# EPS_MPPT_X_OR_MPB.net
KiCad netlist of a schematic drawn in Altium Designer
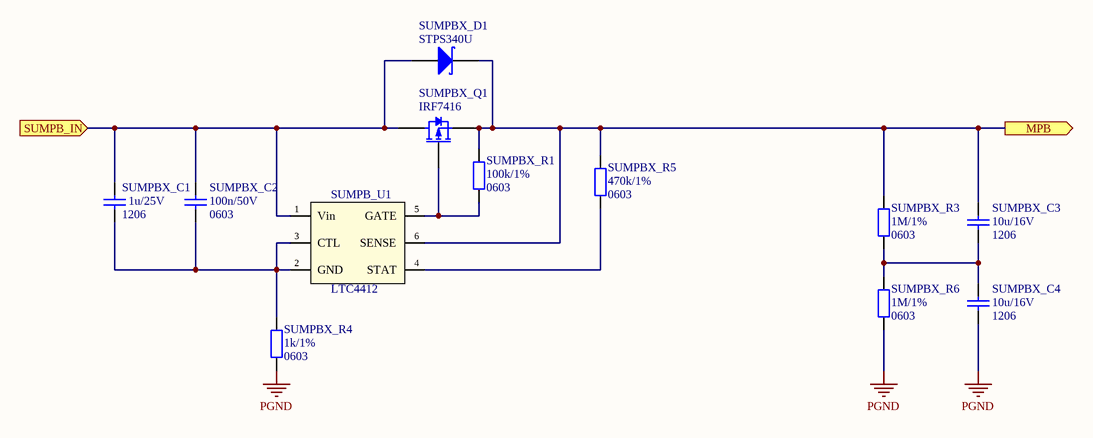
[diagram p0: EPS_MPPT_X_OR_MPB.SchDoc]

(export (version "E")
  (design (tool "Eeschema 10.0.6"))
  (components
    (comp (ref "SUMPBX_C1")
      (value "1u/25V")
      (footprint "SMD_Capacitor_1206")
      (description "Ceramic Cap Kemet COTS 1u/25V X7R 1206")
      (fields
        (field (name "MANUFACTURERPARTNUMBER") "C1206T105K3RALTU")
        (field (name "MANUFACTURER") "Kemet")
        (field (name "PACKAGE") "1206")
      )
      (libsource (lib "capacitors") (part "Cer_C1206T105K3RALTU"))
    )
    (comp (ref "SUMPBX_C2")
      (value "100n/50V")
      (footprint "SMD_Capacitor_0603")
      (description "Ceramic Cap Murata Automotive 100n/50V X7R 0603")
      (fields
        (field (name "MANUFACTURER") "Murata")
        (field (name "MANUFACTURERPARTNUMBER") "GCJ188R71H104KA12D")
        (field (name "PACKAGE") "0603")
      )
      (libsource (lib "capacitors") (part "Cer_GCJ188R71H104KA12D"))
    )
    (comp (ref "SUMPBX_C3")
      (value "10u/16V")
      (footprint "SMD_Capacitor_1206")
      (description "Ceramic Cap Kemet COTS 10u/16V X7R 1206")
      (fields
        (field (name "MANUFACTURERPARTNUMBER") "C1206T106K4RACTU")
        (field (name "MANUFACTURER") "Kemet")
        (field (name "PACKGE") "1206")
      )
      (libsource (lib "capacitors") (part "Cer_C1206T106K4RACTU"))
    )
    (comp (ref "SUMPBX_C4")
      (value "10u/16V")
      (footprint "SMD_Capacitor_1206")
      (description "Ceramic Cap Kemet COTS 10u/16V X7R 1206")
      (fields
        (field (name "MANUFACTURERPARTNUMBER") "C1206T106K4RACTU")
        (field (name "MANUFACTURER") "Kemet")
        (field (name "PACKGE") "1206")
      )
      (libsource (lib "capacitors") (part "Cer_C1206T106K4RACTU"))
    )
    (comp (ref "SUMPBX_D1")
      (value "STPS340U")
      (footprint "DO-214AA")
      (description "3A/40V Power Schottky Rectifier.")
      (fields (field (name "MANUFACTURER") "STMicroelectronics"))
      (libsource (lib "diodes") (part "STPS340x"))
    )
    (comp (ref "SUMPBX_Q1")
      (value "IRF7416")
      (footprint "SOIC-8-N_SSSGDDDD")
      (description "10A/30V HEXFET Power P-MOSFET.")
      (fields (field (name "MANUFACTURER") "International Rectifier"))
      (libsource (lib "transistors") (part "IRF7416"))
    )
    (comp (ref "SUMPBX_R1")
      (value "100k/1%")
      (footprint "SMD_Resistor_0603")
      (fields (field (name "PACKAGE") "0603"))
      (libsource (lib "resistors") (part "Res"))
    )
    (comp (ref "SUMPBX_R3")
      (value "1M/1%")
      (footprint "SMD_Resistor_0603")
      (fields (field (name "PACKAGE") "0603"))
      (libsource (lib "resistors") (part "Res"))
    )
    (comp (ref "SUMPBX_R4")
      (value "1k/1%")
      (footprint "SMD_Resistor_0603")
      (fields (field (name "PACKAGE") "0603"))
      (libsource (lib "resistors") (part "Res"))
    )
    (comp (ref "SUMPBX_R5")
      (value "470k/1%")
      (footprint "SMD_Resistor_0603")
      (fields (field (name "PACKAGE") "0603"))
      (libsource (lib "resistors") (part "Res"))
    )
    (comp (ref "SUMPBX_R6")
      (value "1M/1%")
      (footprint "SMD_Resistor_0603")
      (fields (field (name "PACKAGE") "0603"))
      (libsource (lib "resistors") (part "Res"))
    )
    (comp (ref "SUMPB_U1")
      (value "LTC4412")
      (footprint "SOT23-6")
      (description "Ideal Diode, Low Loss PowerPath Controller.")
      (fields (field (name "MANUFACTURER") "Linear Technology"))
      (libsource (lib "microcircuits") (part "LTC4412"))
    )
  )
  (nets
    (net (code "1") (name "/MPB") (class "Default")
      (node (ref "SUMPBX_C3") (pin "1") (pinfunction "1_1") (pintype "passive"))
      (node (ref "SUMPBX_D1") (pin "K") (pinfunction "K_K") (pintype "passive"))
      (node (ref "SUMPBX_Q1") (pin "S") (pinfunction "S_S") (pintype "passive"))
      (node (ref "SUMPBX_R1") (pin "1") (pinfunction "1_1") (pintype "passive"))
      (node (ref "SUMPBX_R3") (pin "1") (pinfunction "1_1") (pintype "passive"))
      (node (ref "SUMPBX_R5") (pin "1") (pinfunction "1_1") (pintype "passive"))
      (node (ref "SUMPB_U1") (pin "6") (pinfunction "SENSE_6") (pintype "passive"))
    )
    (net (code "2") (name "/SUMPB_IN") (class "Default")
      (node (ref "SUMPBX_C1") (pin "1") (pinfunction "1_1") (pintype "passive"))
      (node (ref "SUMPBX_C2") (pin "1") (pinfunction "1_1") (pintype "passive"))
      (node (ref "SUMPBX_D1") (pin "A") (pinfunction "A_A") (pintype "passive"))
      (node (ref "SUMPBX_Q1") (pin "D") (pinfunction "D_D") (pintype "passive"))
      (node (ref "SUMPB_U1") (pin "1") (pinfunction "Vin_1") (pintype "passive"))
    )
    (net (code "3") (name "Net-(SUMPBX_C3-Pad2)") (class "Default")
      (node (ref "SUMPBX_C3") (pin "2") (pinfunction "2_2") (pintype "passive"))
      (node (ref "SUMPBX_C4") (pin "1") (pinfunction "1_1") (pintype "passive"))
      (node (ref "SUMPBX_R3") (pin "2") (pinfunction "2_2") (pintype "passive"))
      (node (ref "SUMPBX_R6") (pin "1") (pinfunction "1_1") (pintype "passive"))
    )
    (net (code "4") (name "Net-(SUMPB_U1-CTL)") (class "Default")
      (node (ref "SUMPBX_C1") (pin "2") (pinfunction "2_2") (pintype "passive"))
      (node (ref "SUMPBX_C2") (pin "2") (pinfunction "2_2") (pintype "passive"))
      (node (ref "SUMPBX_R4") (pin "1") (pinfunction "1_1") (pintype "passive"))
      (node (ref "SUMPB_U1") (pin "2") (pinfunction "GND_2") (pintype "passive"))
      (node (ref "SUMPB_U1") (pin "3") (pinfunction "CTL_3") (pintype "passive"))
    )
    (net (code "5") (name "Net-(SUMPB_U1-GATE)") (class "Default")
      (node (ref "SUMPBX_Q1") (pin "G") (pinfunction "G_G") (pintype "passive"))
      (node (ref "SUMPBX_R1") (pin "2") (pinfunction "2_2") (pintype "passive"))
      (node (ref "SUMPB_U1") (pin "5") (pinfunction "GATE_5") (pintype "passive"))
    )
    (net (code "6") (name "Net-(SUMPB_U1-STAT)") (class "Default")
      (node (ref "SUMPBX_R5") (pin "2") (pinfunction "2_2") (pintype "passive"))
      (node (ref "SUMPB_U1") (pin "4") (pinfunction "STAT_4") (pintype "passive"))
    )
    (net (code "7") (name "PGND") (class "Default")
      (node (ref "SUMPBX_C4") (pin "2") (pinfunction "2_2") (pintype "passive"))
      (node (ref "SUMPBX_R4") (pin "2") (pinfunction "2_2") (pintype "passive"))
      (node (ref "SUMPBX_R6") (pin "2") (pinfunction "2_2") (pintype "passive"))
    )
  )
)
